# SheetCircuitInputPowerModule220V.net
KiCad netlist of a schematic drawn in Altium Designer
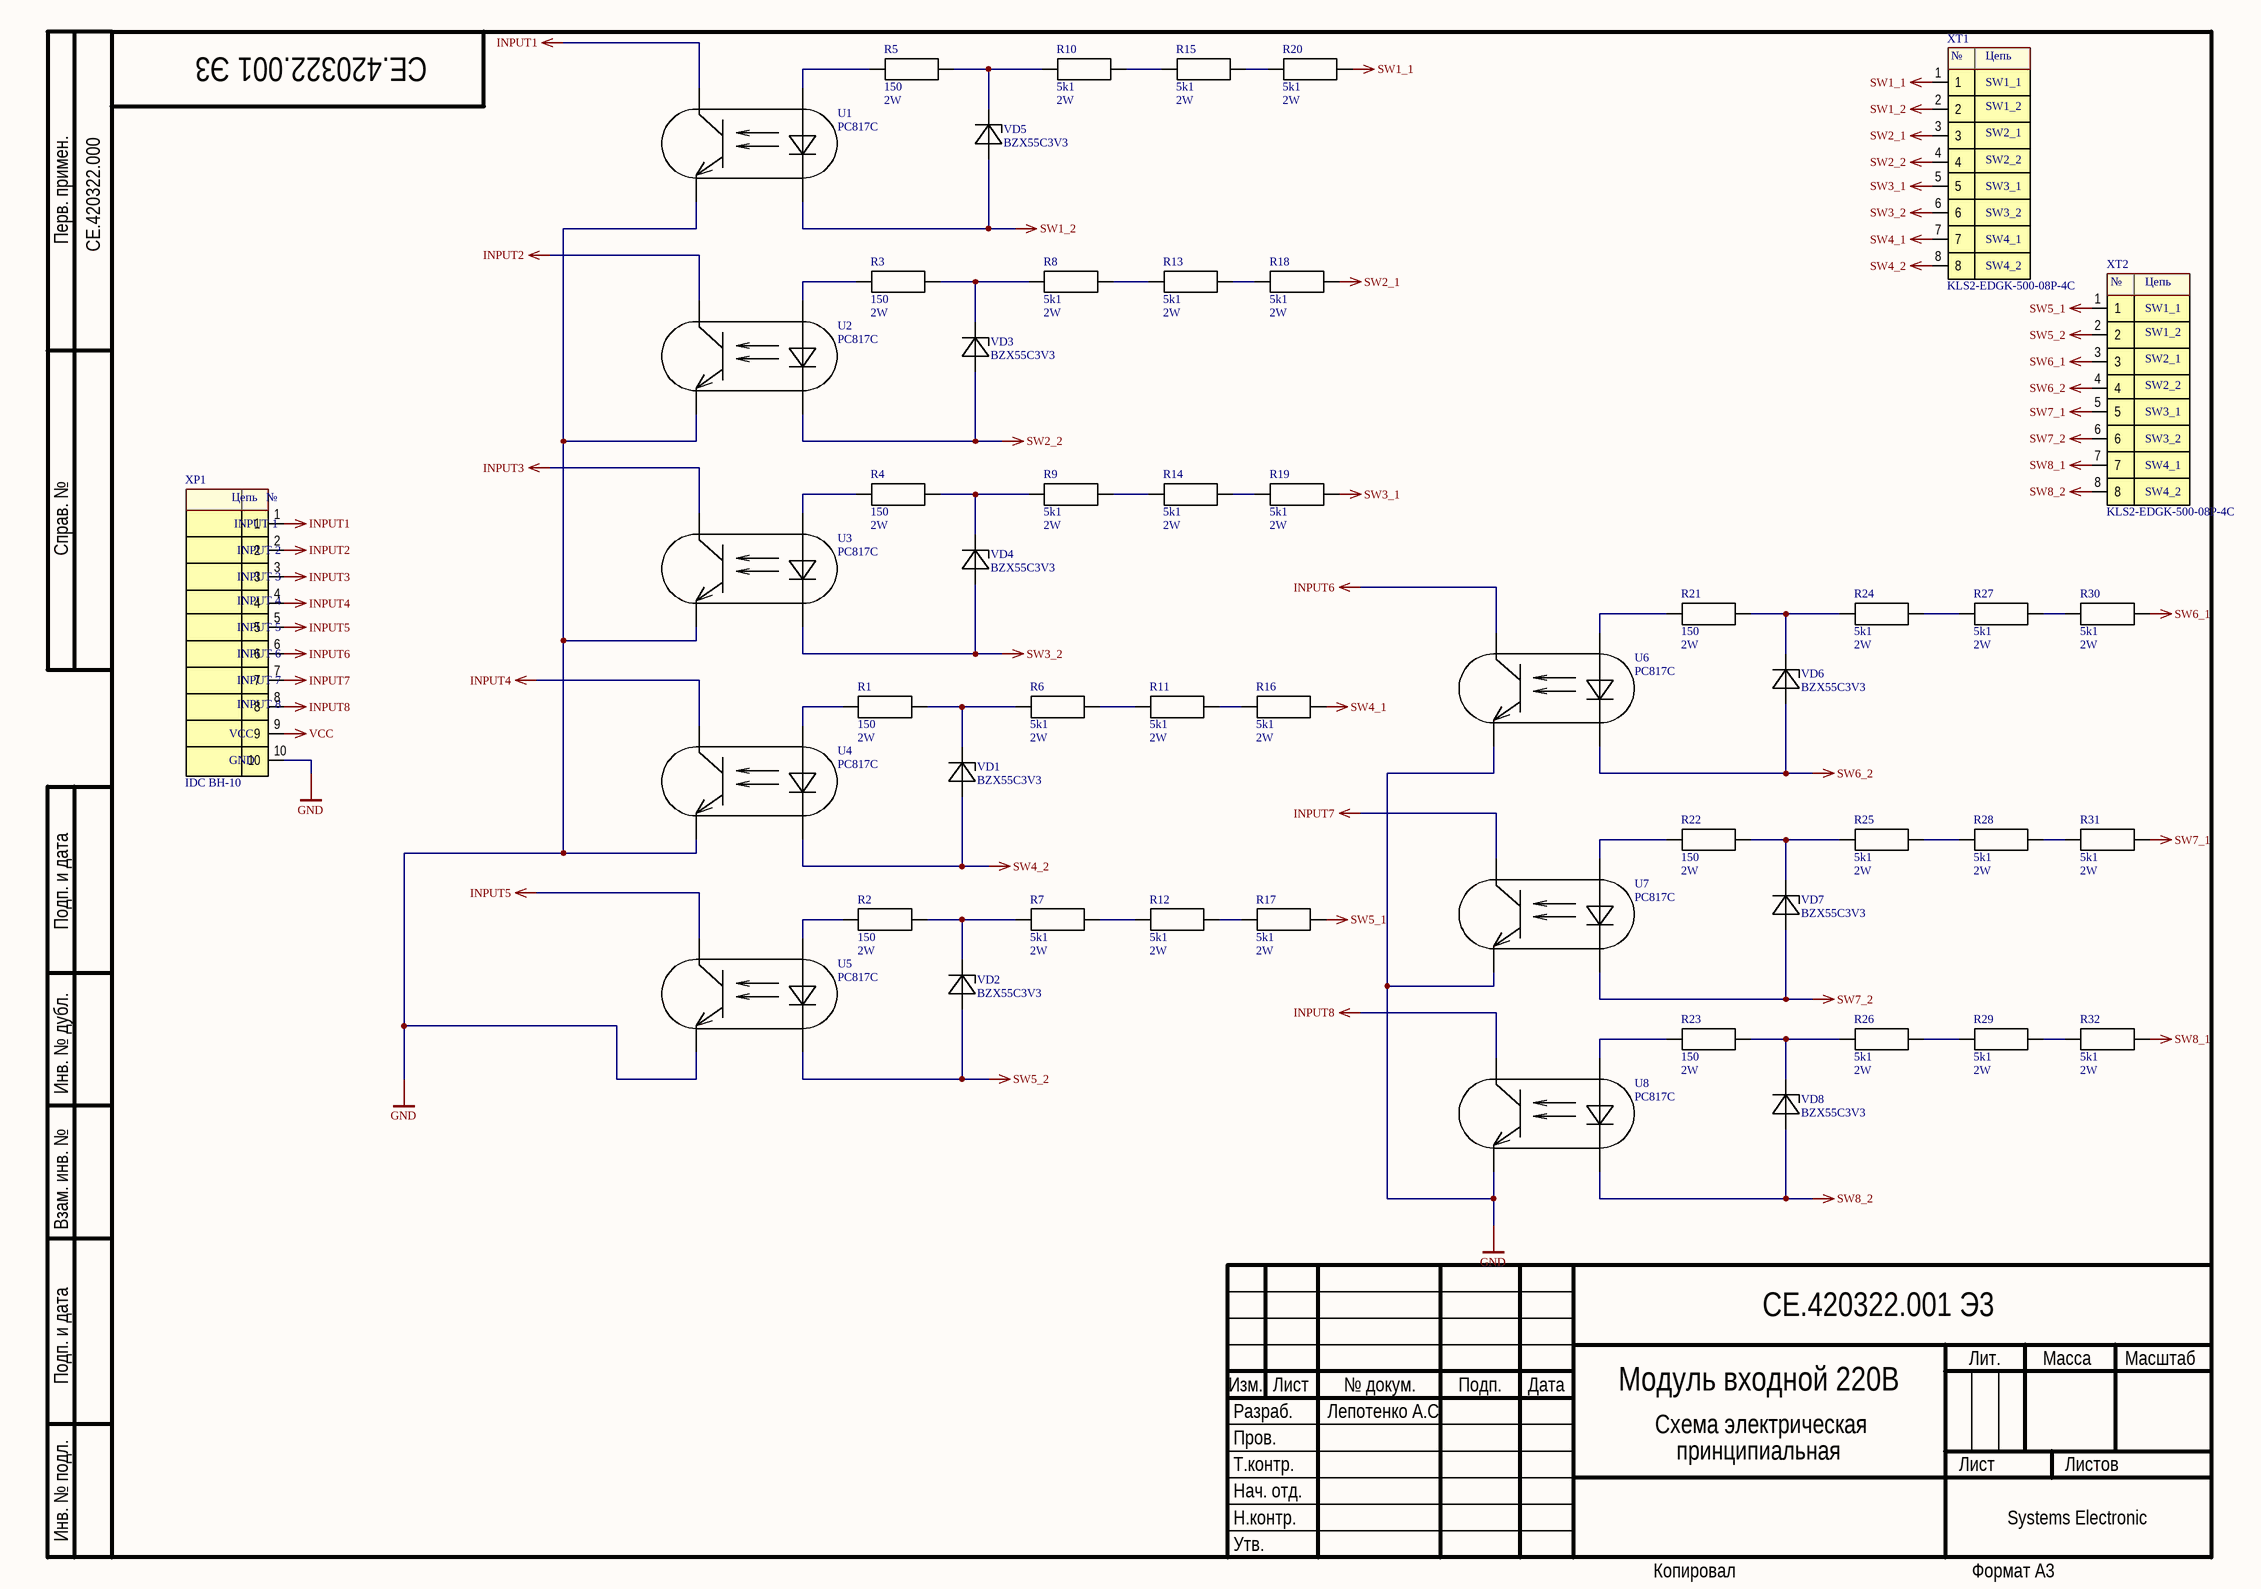
[diagram p0: SheetCircuitInputPowerModule220V.SchDoc]

(export (version "E")
  (design (tool "Eeschema 10.0.6"))
  (components
    (comp (ref "R1")
      (value "150")
      (footprint "MOF-2W-15x5")
      (fields
        (field (name "MANUFACTURER") "Royal Ohm")
        (field (name "PART NUMBER") "CFR02WJ0151P5")
        (field (name "POWER") "2W")
      )
      (libsource (lib "SchlibUGO") (part "Resistor"))
    )
    (comp (ref "R2")
      (value "150")
      (footprint "MOF-2W-15x5")
      (fields
        (field (name "MANUFACTURER") "Royal Ohm")
        (field (name "PART NUMBER") "CFR02WJ0151P5")
        (field (name "POWER") "2W")
      )
      (libsource (lib "SchlibUGO") (part "Resistor"))
    )
    (comp (ref "R3")
      (value "150")
      (footprint "MOF-2W-15x5")
      (fields
        (field (name "MANUFACTURER") "Royal Ohm")
        (field (name "PART NUMBER") "CFR02WJ0151P5")
        (field (name "POWER") "2W")
      )
      (libsource (lib "SchlibUGO") (part "Resistor"))
    )
    (comp (ref "R4")
      (value "150")
      (footprint "MOF-2W-15x5")
      (fields
        (field (name "MANUFACTURER") "Royal Ohm")
        (field (name "PART NUMBER") "CFR02WJ0151P5")
        (field (name "POWER") "2W")
      )
      (libsource (lib "SchlibUGO") (part "Resistor"))
    )
    (comp (ref "R5")
      (value "150")
      (footprint "MOF-2W-15x5")
      (fields
        (field (name "MANUFACTURER") "Royal Ohm")
        (field (name "PART NUMBER") "CFR02WJ0151P5")
        (field (name "POWER") "2W")
      )
      (libsource (lib "SchlibUGO") (part "Resistor"))
    )
    (comp (ref "R6")
      (value "5k1")
      (footprint "MOF-2W-15x5")
      (fields
        (field (name "MANUFACTURER") "Royal Ohm")
        (field (name "PART NUMBER") "CFR02WJ0512P5")
        (field (name "POWER") "2W")
      )
      (libsource (lib "SchlibUGO") (part "Resistor"))
    )
    (comp (ref "R7")
      (value "5k1")
      (footprint "MOF-2W-15x5")
      (fields
        (field (name "MANUFACTURER") "Royal Ohm")
        (field (name "PART NUMBER") "CFR02WJ0512P5")
        (field (name "POWER") "2W")
      )
      (libsource (lib "SchlibUGO") (part "Resistor"))
    )
    (comp (ref "R8")
      (value "5k1")
      (footprint "MOF-2W-15x5")
      (fields
        (field (name "MANUFACTURER") "Royal Ohm")
        (field (name "PART NUMBER") "CFR02WJ0512P5")
        (field (name "POWER") "2W")
      )
      (libsource (lib "SchlibUGO") (part "Resistor"))
    )
    (comp (ref "R9")
      (value "5k1")
      (footprint "MOF-2W-15x5")
      (fields
        (field (name "MANUFACTURER") "Royal Ohm")
        (field (name "PART NUMBER") "CFR02WJ0512P5")
        (field (name "POWER") "2W")
      )
      (libsource (lib "SchlibUGO") (part "Resistor"))
    )
    (comp (ref "R10")
      (value "5k1")
      (footprint "MOF-2W-15x5")
      (fields
        (field (name "MANUFACTURER") "Royal Ohm")
        (field (name "PART NUMBER") "CFR02WJ0512P5")
        (field (name "POWER") "2W")
      )
      (libsource (lib "SchlibUGO") (part "Resistor"))
    )
    (comp (ref "R11")
      (value "5k1")
      (footprint "MOF-2W-15x5")
      (fields
        (field (name "MANUFACTURER") "Royal Ohm")
        (field (name "PART NUMBER") "CFR02WJ0512P5")
        (field (name "POWER") "2W")
      )
      (libsource (lib "SchlibUGO") (part "Resistor"))
    )
    (comp (ref "R12")
      (value "5k1")
      (footprint "MOF-2W-15x5")
      (fields
        (field (name "MANUFACTURER") "Royal Ohm")
        (field (name "PART NUMBER") "CFR02WJ0512P5")
        (field (name "POWER") "2W")
      )
      (libsource (lib "SchlibUGO") (part "Resistor"))
    )
    (comp (ref "R13")
      (value "5k1")
      (footprint "MOF-2W-15x5")
      (fields
        (field (name "MANUFACTURER") "Royal Ohm")
        (field (name "PART NUMBER") "CFR02WJ0512P5")
        (field (name "POWER") "2W")
      )
      (libsource (lib "SchlibUGO") (part "Resistor"))
    )
    (comp (ref "R14")
      (value "5k1")
      (footprint "MOF-2W-15x5")
      (fields
        (field (name "MANUFACTURER") "Royal Ohm")
        (field (name "PART NUMBER") "CFR02WJ0512P5")
        (field (name "POWER") "2W")
      )
      (libsource (lib "SchlibUGO") (part "Resistor"))
    )
    (comp (ref "R15")
      (value "5k1")
      (footprint "MOF-2W-15x5")
      (fields
        (field (name "MANUFACTURER") "Royal Ohm")
        (field (name "PART NUMBER") "CFR02WJ0512P5")
        (field (name "POWER") "2W")
      )
      (libsource (lib "SchlibUGO") (part "Resistor"))
    )
    (comp (ref "R16")
      (value "5k1")
      (footprint "MOF-2W-15x5")
      (fields
        (field (name "MANUFACTURER") "Royal Ohm")
        (field (name "PART NUMBER") "CFR02WJ0512P5")
        (field (name "POWER") "2W")
      )
      (libsource (lib "SchlibUGO") (part "Resistor"))
    )
    (comp (ref "R17")
      (value "5k1")
      (footprint "MOF-2W-15x5")
      (fields
        (field (name "MANUFACTURER") "Royal Ohm")
        (field (name "PART NUMBER") "CFR02WJ0512P5")
        (field (name "POWER") "2W")
      )
      (libsource (lib "SchlibUGO") (part "Resistor"))
    )
    (comp (ref "R18")
      (value "5k1")
      (footprint "MOF-2W-15x5")
      (fields
        (field (name "MANUFACTURER") "Royal Ohm")
        (field (name "PART NUMBER") "CFR02WJ0512P5")
        (field (name "POWER") "2W")
      )
      (libsource (lib "SchlibUGO") (part "Resistor"))
    )
    (comp (ref "R19")
      (value "5k1")
      (footprint "MOF-2W-15x5")
      (fields
        (field (name "MANUFACTURER") "Royal Ohm")
        (field (name "PART NUMBER") "CFR02WJ0512P5")
        (field (name "POWER") "2W")
      )
      (libsource (lib "SchlibUGO") (part "Resistor"))
    )
    (comp (ref "R20")
      (value "5k1")
      (footprint "MOF-2W-15x5")
      (fields
        (field (name "MANUFACTURER") "Royal Ohm")
        (field (name "PART NUMBER") "CFR02WJ0512P5")
        (field (name "POWER") "2W")
      )
      (libsource (lib "SchlibUGO") (part "Resistor"))
    )
    (comp (ref "R21")
      (value "150")
      (footprint "MOF-2W-15x5")
      (fields
        (field (name "MANUFACTURER") "Royal Ohm")
        (field (name "PART NUMBER") "CFR02WJ0151P5")
        (field (name "POWER") "2W")
      )
      (libsource (lib "SchlibUGO") (part "Resistor"))
    )
    (comp (ref "R22")
      (value "150")
      (footprint "MOF-2W-15x5")
      (fields
        (field (name "MANUFACTURER") "Royal Ohm")
        (field (name "PART NUMBER") "CFR02WJ0151P5")
        (field (name "POWER") "2W")
      )
      (libsource (lib "SchlibUGO") (part "Resistor"))
    )
    (comp (ref "R23")
      (value "150")
      (footprint "MOF-2W-15x5")
      (fields
        (field (name "MANUFACTURER") "Royal Ohm")
        (field (name "PART NUMBER") "CFR02WJ0151P5")
        (field (name "POWER") "2W")
      )
      (libsource (lib "SchlibUGO") (part "Resistor"))
    )
    (comp (ref "R24")
      (value "5k1")
      (footprint "MOF-2W-15x5")
      (fields
        (field (name "MANUFACTURER") "Royal Ohm")
        (field (name "PART NUMBER") "CFR02WJ0512P5")
        (field (name "POWER") "2W")
      )
      (libsource (lib "SchlibUGO") (part "Resistor"))
    )
    (comp (ref "R25")
      (value "5k1")
      (footprint "MOF-2W-15x5")
      (fields
        (field (name "MANUFACTURER") "Royal Ohm")
        (field (name "PART NUMBER") "CFR02WJ0512P5")
        (field (name "POWER") "2W")
      )
      (libsource (lib "SchlibUGO") (part "Resistor"))
    )
    (comp (ref "R26")
      (value "5k1")
      (footprint "MOF-2W-15x5")
      (fields
        (field (name "MANUFACTURER") "Royal Ohm")
        (field (name "PART NUMBER") "CFR02WJ0512P5")
        (field (name "POWER") "2W")
      )
      (libsource (lib "SchlibUGO") (part "Resistor"))
    )
    (comp (ref "R27")
      (value "5k1")
      (footprint "MOF-2W-15x5")
      (fields
        (field (name "MANUFACTURER") "Royal Ohm")
        (field (name "PART NUMBER") "CFR02WJ0512P5")
        (field (name "POWER") "2W")
      )
      (libsource (lib "SchlibUGO") (part "Resistor"))
    )
    (comp (ref "R28")
      (value "5k1")
      (footprint "MOF-2W-15x5")
      (fields
        (field (name "MANUFACTURER") "Royal Ohm")
        (field (name "PART NUMBER") "CFR02WJ0512P5")
        (field (name "POWER") "2W")
      )
      (libsource (lib "SchlibUGO") (part "Resistor"))
    )
    (comp (ref "R29")
      (value "5k1")
      (footprint "MOF-2W-15x5")
      (fields
        (field (name "MANUFACTURER") "Royal Ohm")
        (field (name "PART NUMBER") "CFR02WJ0512P5")
        (field (name "POWER") "2W")
      )
      (libsource (lib "SchlibUGO") (part "Resistor"))
    )
    (comp (ref "R30")
      (value "5k1")
      (footprint "MOF-2W-15x5")
      (fields
        (field (name "MANUFACTURER") "Royal Ohm")
        (field (name "PART NUMBER") "CFR02WJ0512P5")
        (field (name "POWER") "2W")
      )
      (libsource (lib "SchlibUGO") (part "Resistor"))
    )
    (comp (ref "R31")
      (value "5k1")
      (footprint "MOF-2W-15x5")
      (fields
        (field (name "MANUFACTURER") "Royal Ohm")
        (field (name "PART NUMBER") "CFR02WJ0512P5")
        (field (name "POWER") "2W")
      )
      (libsource (lib "SchlibUGO") (part "Resistor"))
    )
    (comp (ref "R32")
      (value "5k1")
      (footprint "MOF-2W-15x5")
      (fields
        (field (name "MANUFACTURER") "Royal Ohm")
        (field (name "PART NUMBER") "CFR02WJ0512P5")
        (field (name "POWER") "2W")
      )
      (libsource (lib "SchlibUGO") (part "Resistor"))
    )
    (comp (ref "U1")
      (value "PC817C")
      (footprint "DIP-4M")
      (fields (field (name "MANUFACTURER") "SHARP"))
      (libsource (lib "SchlibUGO") (part "PC817"))
    )
    (comp (ref "U2")
      (value "PC817C")
      (footprint "DIP-4M")
      (fields (field (name "MANUFACTURER") "SHARP"))
      (libsource (lib "SchlibUGO") (part "PC817"))
    )
    (comp (ref "U3")
      (value "PC817C")
      (footprint "DIP-4M")
      (fields (field (name "MANUFACTURER") "SHARP"))
      (libsource (lib "SchlibUGO") (part "PC817"))
    )
    (comp (ref "U4")
      (value "PC817C")
      (footprint "DIP-4M")
      (fields (field (name "MANUFACTURER") "SHARP"))
      (libsource (lib "SchlibUGO") (part "PC817"))
    )
    (comp (ref "U5")
      (value "PC817C")
      (footprint "DIP-4M")
      (fields (field (name "MANUFACTURER") "SHARP"))
      (libsource (lib "SchlibUGO") (part "PC817"))
    )
    (comp (ref "U6")
      (value "PC817C")
      (footprint "DIP-4M")
      (fields (field (name "MANUFACTURER") "SHARP"))
      (libsource (lib "SchlibUGO") (part "PC817"))
    )
    (comp (ref "U7")
      (value "PC817C")
      (footprint "DIP-4M")
      (fields (field (name "MANUFACTURER") "SHARP"))
      (libsource (lib "SchlibUGO") (part "PC817"))
    )
    (comp (ref "U8")
      (value "PC817C")
      (footprint "DIP-4M")
      (fields (field (name "MANUFACTURER") "SHARP"))
      (libsource (lib "SchlibUGO") (part "PC817"))
    )
    (comp (ref "VD1")
      (value "BZX55C3V3")
      (footprint "DO-35")
      (fields (field (name "MANUFACTURER") "DC Components"))
      (libsource (lib "SchlibUGO") (part "Stabilitron"))
    )
    (comp (ref "VD2")
      (value "BZX55C3V3")
      (footprint "DO-35")
      (fields (field (name "MANUFACTURER") "DC Components"))
      (libsource (lib "SchlibUGO") (part "Stabilitron"))
    )
    (comp (ref "VD3")
      (value "BZX55C3V3")
      (footprint "DO-35")
      (fields (field (name "MANUFACTURER") "DC Components"))
      (libsource (lib "SchlibUGO") (part "Stabilitron"))
    )
    (comp (ref "VD4")
      (value "BZX55C3V3")
      (footprint "DO-35")
      (fields (field (name "MANUFACTURER") "DC Components"))
      (libsource (lib "SchlibUGO") (part "Stabilitron"))
    )
    (comp (ref "VD5")
      (value "BZX55C3V3")
      (footprint "DO-35")
      (fields (field (name "MANUFACTURER") "DC Components"))
      (libsource (lib "SchlibUGO") (part "Stabilitron"))
    )
    (comp (ref "VD6")
      (value "BZX55C3V3")
      (footprint "DO-35")
      (fields (field (name "MANUFACTURER") "DC Components"))
      (libsource (lib "SchlibUGO") (part "Stabilitron"))
    )
    (comp (ref "VD7")
      (value "BZX55C3V3")
      (footprint "DO-35")
      (fields (field (name "MANUFACTURER") "DC Components"))
      (libsource (lib "SchlibUGO") (part "Stabilitron"))
    )
    (comp (ref "VD8")
      (value "BZX55C3V3")
      (footprint "DO-35")
      (fields (field (name "MANUFACTURER") "DC Components"))
      (libsource (lib "SchlibUGO") (part "Stabilitron"))
    )
    (comp (ref "XP1")
      (value "IDC BH-10")
      (footprint "IDC-10-2")
      (fields (field (name "MANUFACTURER") "RUICHI"))
      (libsource (lib "SchlibUGO") (part "Разъем IDC BH-10"))
    )
    (comp (ref "XT1")
      (value "KLS2-EDGK-500-08P-4C")
      (footprint "KLS2-EDR-500-8P")
      (fields (field (name "MANUFACTURER") "KLS"))
      (libsource (lib "SchlibUGO") (part "KLS2-EDGK-500-08P-4C"))
    )
    (comp (ref "XT2")
      (value "KLS2-EDGK-500-08P-4C")
      (footprint "KLS2-EDR-500-8P")
      (fields (field (name "MANUFACTURER") "KLS"))
      (libsource (lib "SchlibUGO") (part "KLS2-EDGK-500-08P-4C"))
    )
  )
  (nets
    (net (code "1") (name "GND") (class "Default")
      (node (ref "U1") (pin "3") (pinfunction "3_3") (pintype "passive"))
      (node (ref "U2") (pin "3") (pinfunction "3_3") (pintype "passive"))
      (node (ref "U3") (pin "3") (pinfunction "3_3") (pintype "passive"))
      (node (ref "U4") (pin "3") (pinfunction "3_3") (pintype "passive"))
      (node (ref "U5") (pin "3") (pinfunction "3_3") (pintype "passive"))
      (node (ref "U6") (pin "3") (pinfunction "3_3") (pintype "passive"))
      (node (ref "U7") (pin "3") (pinfunction "3_3") (pintype "passive"))
      (node (ref "U8") (pin "3") (pinfunction "3_3") (pintype "passive"))
      (node (ref "XP1") (pin "10") (pinfunction "10_10") (pintype "passive"))
    )
    (net (code "2") (name "INPUT1") (class "Default")
      (node (ref "U1") (pin "4") (pinfunction "4_4") (pintype "passive"))
      (node (ref "XP1") (pin "1") (pinfunction "1_1") (pintype "passive"))
    )
    (net (code "3") (name "INPUT2") (class "Default")
      (node (ref "U2") (pin "4") (pinfunction "4_4") (pintype "passive"))
      (node (ref "XP1") (pin "2") (pinfunction "2_2") (pintype "passive"))
    )
    (net (code "4") (name "INPUT3") (class "Default")
      (node (ref "U3") (pin "4") (pinfunction "4_4") (pintype "passive"))
      (node (ref "XP1") (pin "3") (pinfunction "3_3") (pintype "passive"))
    )
    (net (code "5") (name "INPUT4") (class "Default")
      (node (ref "U4") (pin "4") (pinfunction "4_4") (pintype "passive"))
      (node (ref "XP1") (pin "4") (pinfunction "4_4") (pintype "passive"))
    )
    (net (code "6") (name "INPUT5") (class "Default")
      (node (ref "U5") (pin "4") (pinfunction "4_4") (pintype "passive"))
      (node (ref "XP1") (pin "5") (pinfunction "5_5") (pintype "passive"))
    )
    (net (code "7") (name "INPUT6") (class "Default")
      (node (ref "U6") (pin "4") (pinfunction "4_4") (pintype "passive"))
      (node (ref "XP1") (pin "6") (pinfunction "6_6") (pintype "passive"))
    )
    (net (code "8") (name "INPUT7") (class "Default")
      (node (ref "U7") (pin "4") (pinfunction "4_4") (pintype "passive"))
      (node (ref "XP1") (pin "7") (pinfunction "7_7") (pintype "passive"))
    )
    (net (code "9") (name "INPUT8") (class "Default")
      (node (ref "U8") (pin "4") (pinfunction "4_4") (pintype "passive"))
      (node (ref "XP1") (pin "8") (pinfunction "8_8") (pintype "passive"))
    )
    (net (code "10") (name "Net-(R1-Pad1)") (class "Default")
      (node (ref "R1") (pin "1") (pinfunction "1_1") (pintype "passive"))
      (node (ref "U4") (pin "1") (pinfunction "1_1") (pintype "passive"))
    )
    (net (code "11") (name "Net-(R1-Pad2)") (class "Default")
      (node (ref "R1") (pin "2") (pinfunction "2_2") (pintype "passive"))
      (node (ref "R6") (pin "1") (pinfunction "1_1") (pintype "passive"))
      (node (ref "VD1") (pin "2") (pinfunction "2_2") (pintype "passive"))
    )
    (net (code "12") (name "Net-(R2-Pad1)") (class "Default")
      (node (ref "R2") (pin "1") (pinfunction "1_1") (pintype "passive"))
      (node (ref "U5") (pin "1") (pinfunction "1_1") (pintype "passive"))
    )
    (net (code "13") (name "Net-(R2-Pad2)") (class "Default")
      (node (ref "R2") (pin "2") (pinfunction "2_2") (pintype "passive"))
      (node (ref "R7") (pin "1") (pinfunction "1_1") (pintype "passive"))
      (node (ref "VD2") (pin "2") (pinfunction "2_2") (pintype "passive"))
    )
    (net (code "14") (name "Net-(R3-Pad1)") (class "Default")
      (node (ref "R3") (pin "1") (pinfunction "1_1") (pintype "passive"))
      (node (ref "U2") (pin "1") (pinfunction "1_1") (pintype "passive"))
    )
    (net (code "15") (name "Net-(R3-Pad2)") (class "Default")
      (node (ref "R3") (pin "2") (pinfunction "2_2") (pintype "passive"))
      (node (ref "R8") (pin "1") (pinfunction "1_1") (pintype "passive"))
      (node (ref "VD3") (pin "2") (pinfunction "2_2") (pintype "passive"))
    )
    (net (code "16") (name "Net-(R4-Pad1)") (class "Default")
      (node (ref "R4") (pin "1") (pinfunction "1_1") (pintype "passive"))
      (node (ref "U3") (pin "1") (pinfunction "1_1") (pintype "passive"))
    )
    (net (code "17") (name "Net-(R4-Pad2)") (class "Default")
      (node (ref "R4") (pin "2") (pinfunction "2_2") (pintype "passive"))
      (node (ref "R9") (pin "1") (pinfunction "1_1") (pintype "passive"))
      (node (ref "VD4") (pin "2") (pinfunction "2_2") (pintype "passive"))
    )
    (net (code "18") (name "Net-(R5-Pad1)") (class "Default")
      (node (ref "R5") (pin "1") (pinfunction "1_1") (pintype "passive"))
      (node (ref "U1") (pin "1") (pinfunction "1_1") (pintype "passive"))
    )
    (net (code "19") (name "Net-(R10-Pad1)") (class "Default")
      (node (ref "R10") (pin "1") (pinfunction "1_1") (pintype "passive"))
      (node (ref "R5") (pin "2") (pinfunction "2_2") (pintype "passive"))
      (node (ref "VD5") (pin "2") (pinfunction "2_2") (pintype "passive"))
    )
    (net (code "20") (name "Net-(R10-Pad2)") (class "Default")
      (node (ref "R10") (pin "2") (pinfunction "2_2") (pintype "passive"))
      (node (ref "R15") (pin "1") (pinfunction "1_1") (pintype "passive"))
    )
    (net (code "21") (name "Net-(R11-Pad1)") (class "Default")
      (node (ref "R11") (pin "1") (pinfunction "1_1") (pintype "passive"))
      (node (ref "R6") (pin "2") (pinfunction "2_2") (pintype "passive"))
    )
    (net (code "22") (name "Net-(R11-Pad2)") (class "Default")
      (node (ref "R11") (pin "2") (pinfunction "2_2") (pintype "passive"))
      (node (ref "R16") (pin "1") (pinfunction "1_1") (pintype "passive"))
    )
    (net (code "23") (name "Net-(R12-Pad1)") (class "Default")
      (node (ref "R12") (pin "1") (pinfunction "1_1") (pintype "passive"))
      (node (ref "R7") (pin "2") (pinfunction "2_2") (pintype "passive"))
    )
    (net (code "24") (name "Net-(R12-Pad2)") (class "Default")
      (node (ref "R12") (pin "2") (pinfunction "2_2") (pintype "passive"))
      (node (ref "R17") (pin "1") (pinfunction "1_1") (pintype "passive"))
    )
    (net (code "25") (name "Net-(R13-Pad1)") (class "Default")
      (node (ref "R13") (pin "1") (pinfunction "1_1") (pintype "passive"))
      (node (ref "R8") (pin "2") (pinfunction "2_2") (pintype "passive"))
    )
    (net (code "26") (name "Net-(R13-Pad2)") (class "Default")
      (node (ref "R13") (pin "2") (pinfunction "2_2") (pintype "passive"))
      (node (ref "R18") (pin "1") (pinfunction "1_1") (pintype "passive"))
    )
    (net (code "27") (name "Net-(R14-Pad1)") (class "Default")
      (node (ref "R14") (pin "1") (pinfunction "1_1") (pintype "passive"))
      (node (ref "R9") (pin "2") (pinfunction "2_2") (pintype "passive"))
    )
    (net (code "28") (name "Net-(R14-Pad2)") (class "Default")
      (node (ref "R14") (pin "2") (pinfunction "2_2") (pintype "passive"))
      (node (ref "R19") (pin "1") (pinfunction "1_1") (pintype "passive"))
    )
    (net (code "29") (name "Net-(R15-Pad2)") (class "Default")
      (node (ref "R15") (pin "2") (pinfunction "2_2") (pintype "passive"))
      (node (ref "R20") (pin "1") (pinfunction "1_1") (pintype "passive"))
    )
    (net (code "30") (name "Net-(R21-Pad1)") (class "Default")
      (node (ref "R21") (pin "1") (pinfunction "1_1") (pintype "passive"))
      (node (ref "U6") (pin "1") (pinfunction "1_1") (pintype "passive"))
    )
    (net (code "31") (name "Net-(R21-Pad2)") (class "Default")
      (node (ref "R21") (pin "2") (pinfunction "2_2") (pintype "passive"))
      (node (ref "R24") (pin "1") (pinfunction "1_1") (pintype "passive"))
      (node (ref "VD6") (pin "2") (pinfunction "2_2") (pintype "passive"))
    )
    (net (code "32") (name "Net-(R22-Pad1)") (class "Default")
      (node (ref "R22") (pin "1") (pinfunction "1_1") (pintype "passive"))
      (node (ref "U7") (pin "1") (pinfunction "1_1") (pintype "passive"))
    )
    (net (code "33") (name "Net-(R22-Pad2)") (class "Default")
      (node (ref "R22") (pin "2") (pinfunction "2_2") (pintype "passive"))
      (node (ref "R25") (pin "1") (pinfunction "1_1") (pintype "passive"))
      (node (ref "VD7") (pin "2") (pinfunction "2_2") (pintype "passive"))
    )
    (net (code "34") (name "Net-(R23-Pad1)") (class "Default")
      (node (ref "R23") (pin "1") (pinfunction "1_1") (pintype "passive"))
      (node (ref "U8") (pin "1") (pinfunction "1_1") (pintype "passive"))
    )
    (net (code "35") (name "Net-(R23-Pad2)") (class "Default")
      (node (ref "R23") (pin "2") (pinfunction "2_2") (pintype "passive"))
      (node (ref "R26") (pin "1") (pinfunction "1_1") (pintype "passive"))
      (node (ref "VD8") (pin "2") (pinfunction "2_2") (pintype "passive"))
    )
    (net (code "36") (name "Net-(R24-Pad2)") (class "Default")
      (node (ref "R24") (pin "2") (pinfunction "2_2") (pintype "passive"))
      (node (ref "R27") (pin "1") (pinfunction "1_1") (pintype "passive"))
    )
    (net (code "37") (name "Net-(R25-Pad2)") (class "Default")
      (node (ref "R25") (pin "2") (pinfunction "2_2") (pintype "passive"))
      (node (ref "R28") (pin "1") (pinfunction "1_1") (pintype "passive"))
    )
    (net (code "38") (name "Net-(R26-Pad2)") (class "Default")
      (node (ref "R26") (pin "2") (pinfunction "2_2") (pintype "passive"))
      (node (ref "R29") (pin "1") (pinfunction "1_1") (pintype "passive"))
    )
    (net (code "39") (name "Net-(R27-Pad2)") (class "Default")
      (node (ref "R27") (pin "2") (pinfunction "2_2") (pintype "passive"))
      (node (ref "R30") (pin "1") (pinfunction "1_1") (pintype "passive"))
    )
    (net (code "40") (name "Net-(R28-Pad2)") (class "Default")
      (node (ref "R28") (pin "2") (pinfunction "2_2") (pintype "passive"))
      (node (ref "R31") (pin "1") (pinfunction "1_1") (pintype "passive"))
    )
    (net (code "41") (name "Net-(R29-Pad2)") (class "Default")
      (node (ref "R29") (pin "2") (pinfunction "2_2") (pintype "passive"))
      (node (ref "R32") (pin "1") (pinfunction "1_1") (pintype "passive"))
    )
    (net (code "42") (name "SW1_1") (class "Default")
      (node (ref "R20") (pin "2") (pinfunction "2_2") (pintype "passive"))
      (node (ref "XT1") (pin "1") (pinfunction "1_1") (pintype "passive"))
    )
    (net (code "43") (name "SW1_2") (class "Default")
      (node (ref "U1") (pin "2") (pinfunction "2_2") (pintype "passive"))
      (node (ref "VD5") (pin "1") (pinfunction "1_1") (pintype "passive"))
      (node (ref "XT1") (pin "2") (pinfunction "2_2") (pintype "passive"))
    )
    (net (code "44") (name "SW2_1") (class "Default")
      (node (ref "R18") (pin "2") (pinfunction "2_2") (pintype "passive"))
      (node (ref "XT1") (pin "3") (pinfunction "3_3") (pintype "passive"))
    )
    (net (code "45") (name "SW2_2") (class "Default")
      (node (ref "U2") (pin "2") (pinfunction "2_2") (pintype "passive"))
      (node (ref "VD3") (pin "1") (pinfunction "1_1") (pintype "passive"))
      (node (ref "XT1") (pin "4") (pinfunction "4_4") (pintype "passive"))
    )
    (net (code "46") (name "SW3_1") (class "Default")
      (node (ref "R19") (pin "2") (pinfunction "2_2") (pintype "passive"))
      (node (ref "XT1") (pin "5") (pinfunction "5_5") (pintype "passive"))
    )
    (net (code "47") (name "SW3_2") (class "Default")
      (node (ref "U3") (pin "2") (pinfunction "2_2") (pintype "passive"))
      (node (ref "VD4") (pin "1") (pinfunction "1_1") (pintype "passive"))
      (node (ref "XT1") (pin "6") (pinfunction "6_6") (pintype "passive"))
    )
    (net (code "48") (name "SW4_1") (class "Default")
      (node (ref "R16") (pin "2") (pinfunction "2_2") (pintype "passive"))
      (node (ref "XT1") (pin "7") (pinfunction "7_7") (pintype "passive"))
    )
    (net (code "49") (name "SW4_2") (class "Default")
      (node (ref "U4") (pin "2") (pinfunction "2_2") (pintype "passive"))
      (node (ref "VD1") (pin "1") (pinfunction "1_1") (pintype "passive"))
      (node (ref "XT1") (pin "8") (pinfunction "8_8") (pintype "passive"))
    )
    (net (code "50") (name "SW5_1") (class "Default")
      (node (ref "R17") (pin "2") (pinfunction "2_2") (pintype "passive"))
      (node (ref "XT2") (pin "1") (pinfunction "1_1") (pintype "passive"))
    )
    (net (code "51") (name "SW5_2") (class "Default")
      (node (ref "U5") (pin "2") (pinfunction "2_2") (pintype "passive"))
      (node (ref "VD2") (pin "1") (pinfunction "1_1") (pintype "passive"))
      (node (ref "XT2") (pin "2") (pinfunction "2_2") (pintype "passive"))
    )
    (net (code "52") (name "SW6_1") (class "Default")
      (node (ref "R30") (pin "2") (pinfunction "2_2") (pintype "passive"))
      (node (ref "XT2") (pin "3") (pinfunction "3_3") (pintype "passive"))
    )
    (net (code "53") (name "SW6_2") (class "Default")
      (node (ref "U6") (pin "2") (pinfunction "2_2") (pintype "passive"))
      (node (ref "VD6") (pin "1") (pinfunction "1_1") (pintype "passive"))
      (node (ref "XT2") (pin "4") (pinfunction "4_4") (pintype "passive"))
    )
    (net (code "54") (name "SW7_1") (class "Default")
      (node (ref "R31") (pin "2") (pinfunction "2_2") (pintype "passive"))
      (node (ref "XT2") (pin "5") (pinfunction "5_5") (pintype "passive"))
    )
    (net (code "55") (name "SW7_2") (class "Default")
      (node (ref "U7") (pin "2") (pinfunction "2_2") (pintype "passive"))
      (node (ref "VD7") (pin "1") (pinfunction "1_1") (pintype "passive"))
      (node (ref "XT2") (pin "6") (pinfunction "6_6") (pintype "passive"))
    )
    (net (code "56") (name "SW8_1") (class "Default")
      (node (ref "R32") (pin "2") (pinfunction "2_2") (pintype "passive"))
      (node (ref "XT2") (pin "7") (pinfunction "7_7") (pintype "passive"))
    )
    (net (code "57") (name "SW8_2") (class "Default")
      (node (ref "U8") (pin "2") (pinfunction "2_2") (pintype "passive"))
      (node (ref "VD8") (pin "1") (pinfunction "1_1") (pintype "passive"))
      (node (ref "XT2") (pin "8") (pinfunction "8_8") (pintype "passive"))
    )
    (net (code "58") (name "VCC") (class "Default")
      (node (ref "XP1") (pin "9") (pinfunction "9_9") (pintype "passive"))
    )
  )
)
